# FPGA_CODECS.net
KiCad netlist of a schematic drawn in Altium Designer
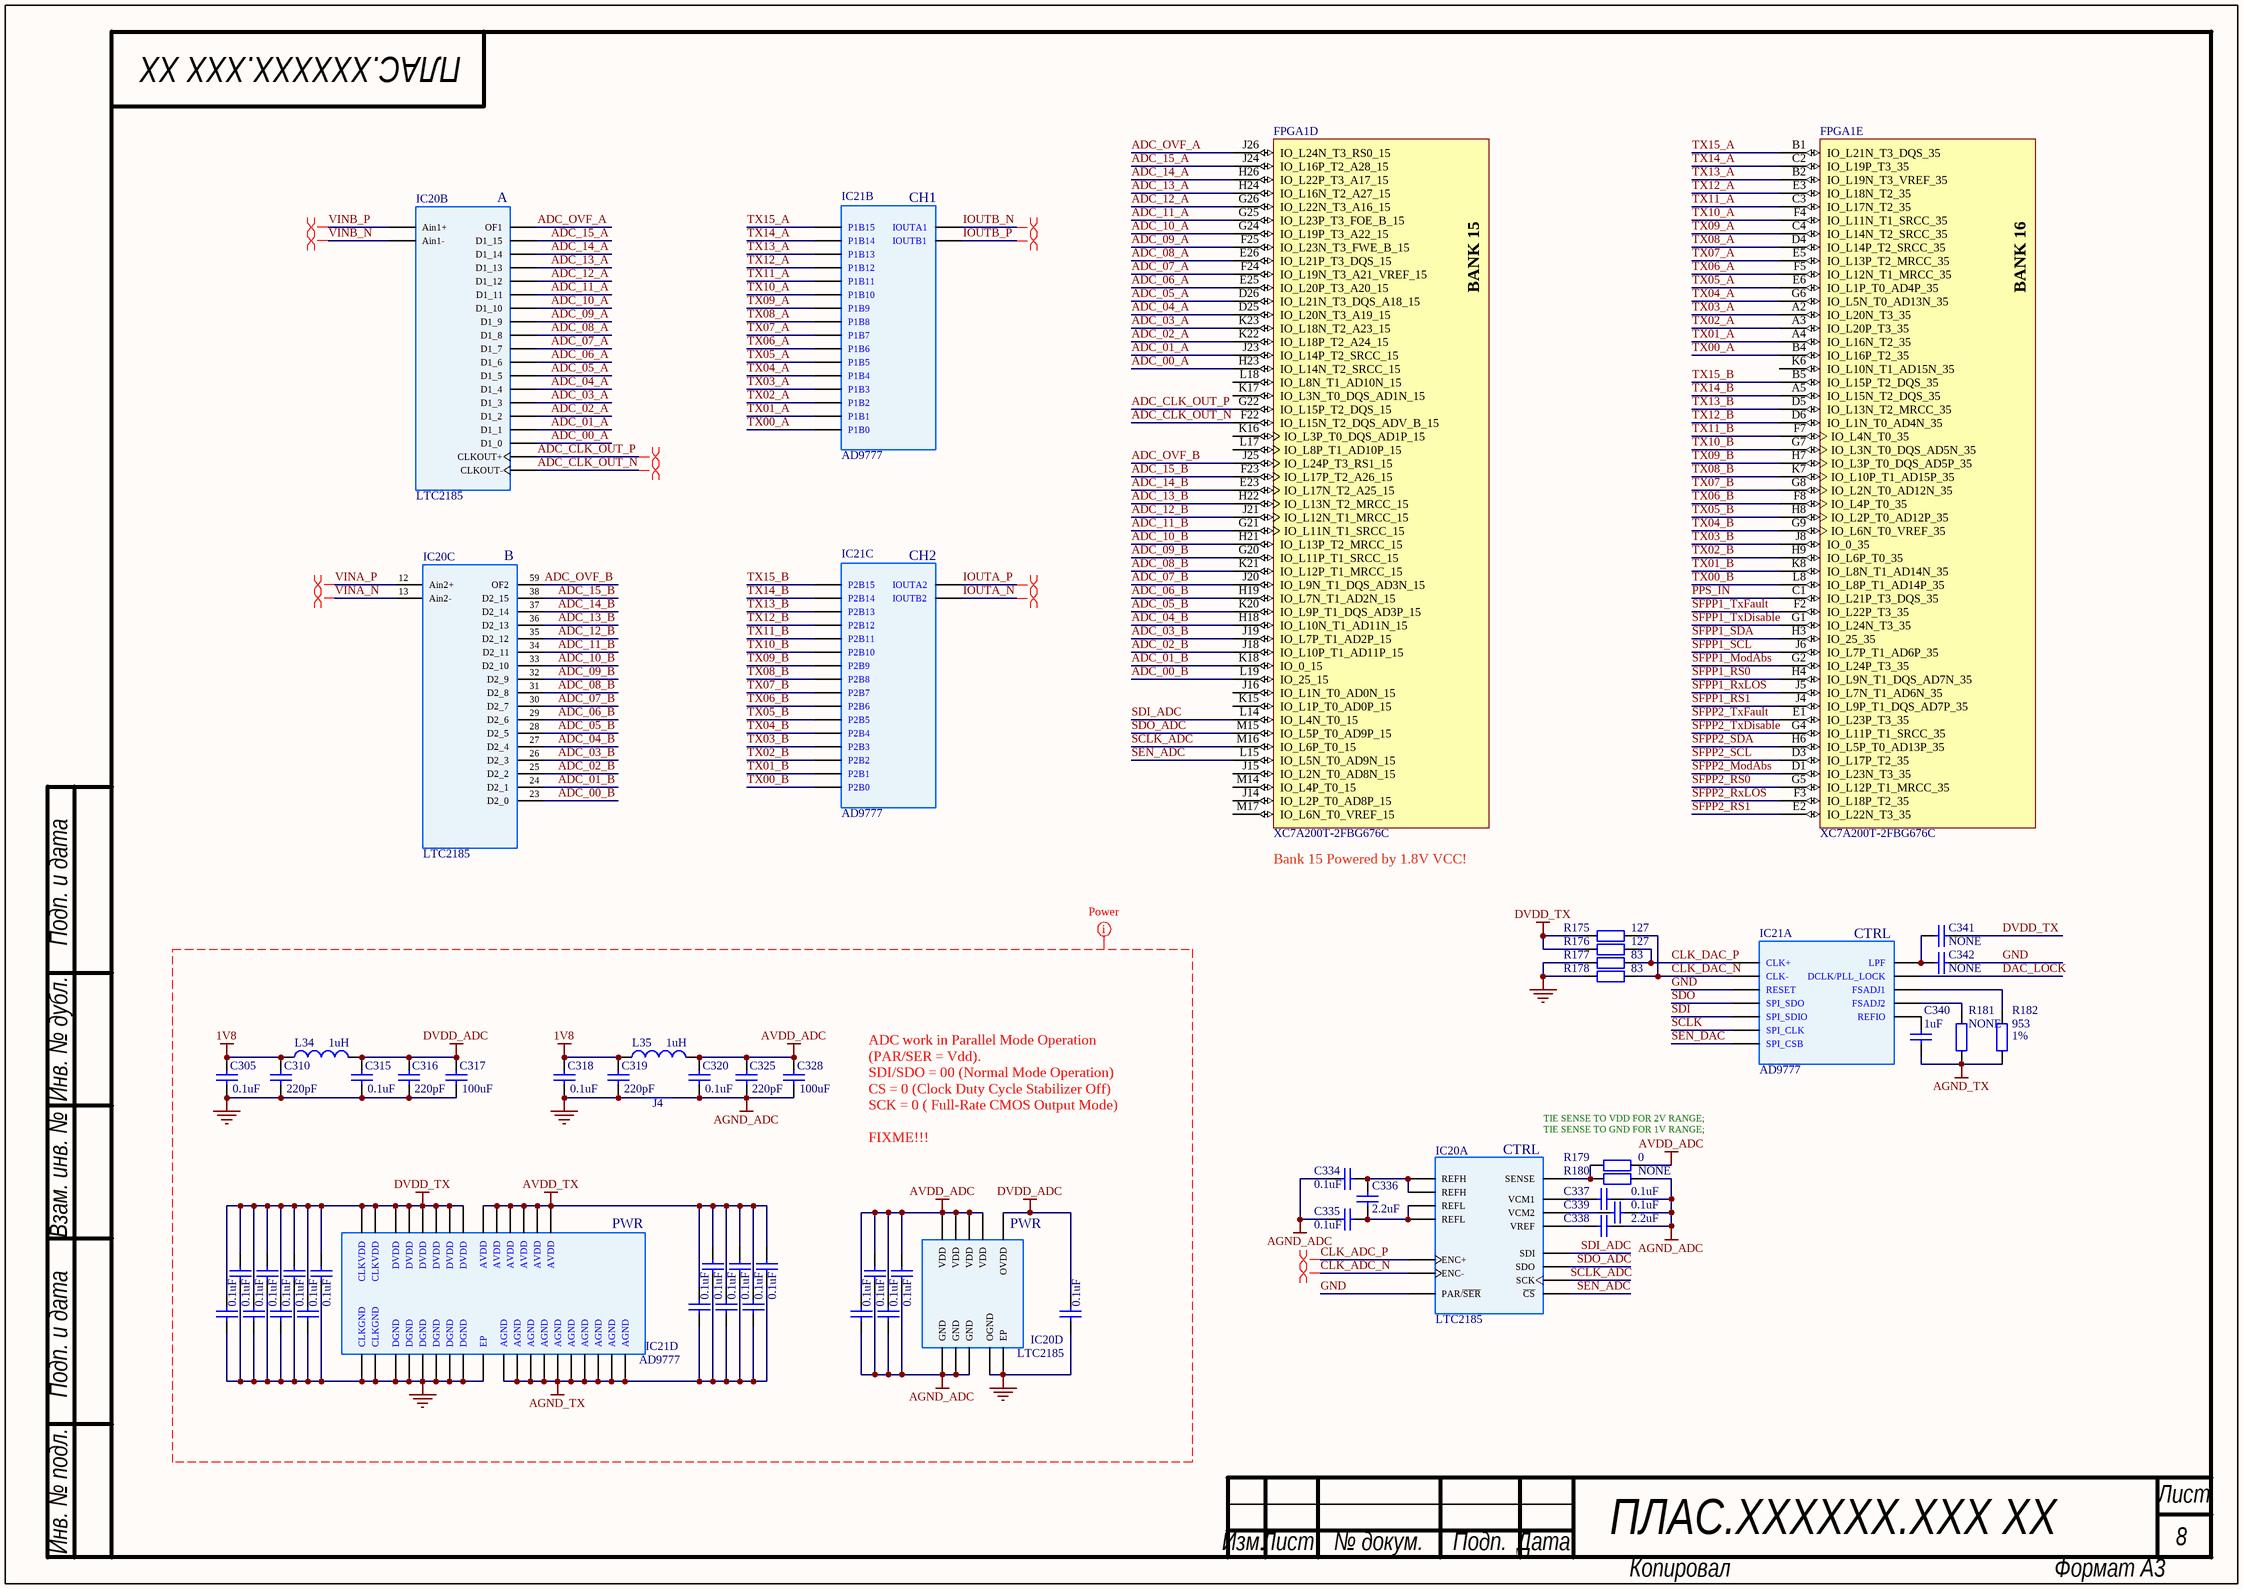
[diagram p0: FPGA&CODECS.SchDoc]

(export (version "E")
  (design (tool "Eeschema 10.0.6"))
  (components
    (comp (ref "C305")
      (value "0.1uF")
      (footprint "C0603")
      (description "Cer Cap Small")
      (fields (field (name "MANUFACTURER") "Murata") (field (name "VOLTAGE") "16V"))
      (libsource (lib "") (part "Cer Cap_1"))
    )
    (comp (ref "C306")
      (value "0.1uF")
      (footprint "С0402")
      (description "Cer Cap Small")
      (fields (field (name "MANUFACTURER") "Murata") (field (name "VOLTAGE") "50V"))
      (libsource (lib "") (part "Cer Cap_1"))
    )
    (comp (ref "C307")
      (value "0.1uF")
      (footprint "С0402")
      (description "Cer Cap Small")
      (fields (field (name "MANUFACTURER") "Murata") (field (name "VOLTAGE") "50V"))
      (libsource (lib "") (part "Cer Cap_1"))
    )
    (comp (ref "C308")
      (value "0.1uF")
      (footprint "С0402")
      (description "Cer Cap Small")
      (fields (field (name "MANUFACTURER") "Murata") (field (name "VOLTAGE") "50V"))
      (libsource (lib "") (part "Cer Cap_1"))
    )
    (comp (ref "C309")
      (value "0.1uF")
      (footprint "С0402")
      (description "Cer Cap Small")
      (fields (field (name "MANUFACTURER") "Murata") (field (name "VOLTAGE") "50V"))
      (libsource (lib "") (part "Cer Cap_1"))
    )
    (comp (ref "C310")
      (value "220pF")
      (footprint "C0603")
      (description "Cer Cap Small")
      (fields (field (name "MANUFACTURER") "Murata") (field (name "VOLTAGE") "16V"))
      (libsource (lib "") (part "Cer Cap_1"))
    )
    (comp (ref "C311")
      (value "0.1uF")
      (footprint "С0402")
      (description "Cer Cap Small")
      (fields (field (name "MANUFACTURER") "Murata") (field (name "VOLTAGE") "50V"))
      (libsource (lib "") (part "Cer Cap_1"))
    )
    (comp (ref "C312")
      (value "0.1uF")
      (footprint "С0402")
      (description "Cer Cap Small")
      (fields (field (name "MANUFACTURER") "Murata") (field (name "VOLTAGE") "50V"))
      (libsource (lib "USRP2_Clone") (part "Cer Cap"))
    )
    (comp (ref "C313")
      (value "0.1uF")
      (footprint "С0402")
      (description "Cer Cap Small")
      (fields (field (name "MANUFACTURER") "Murata") (field (name "VOLTAGE") "50V"))
      (libsource (lib "") (part "Cer Cap_1"))
    )
    (comp (ref "C314")
      (value "0.1uF")
      (footprint "С0402")
      (description "Cer Cap Small")
      (fields (field (name "MANUFACTURER") "Murata") (field (name "VOLTAGE") "50V"))
      (libsource (lib "USRP2_Clone") (part "Cer Cap"))
    )
    (comp (ref "C315")
      (value "0.1uF")
      (footprint "C0603")
      (description "Cer Cap Small")
      (fields (field (name "MANUFACTURER") "Murata") (field (name "VOLTAGE") "16V"))
      (libsource (lib "") (part "Cer Cap_1"))
    )
    (comp (ref "C316")
      (value "220pF")
      (footprint "C0603")
      (description "Cer Cap Small")
      (fields (field (name "MANUFACTURER") "Murata") (field (name "VOLTAGE") "16V"))
      (libsource (lib "") (part "Cer Cap_1"))
    )
    (comp (ref "C317")
      (value "100uF")
      (footprint "C1210")
      (description "Cer Cap Large")
      (fields (field (name "MANUFACTURER") "Murata") (field (name "TOLERANCE") "20%"))
      (libsource (lib "USRP2_Clone") (part "Cap uF"))
    )
    (comp (ref "C318")
      (value "0.1uF")
      (footprint "C0603")
      (description "Cer Cap Small")
      (fields (field (name "MANUFACTURER") "Murata") (field (name "VOLTAGE") "16V"))
      (libsource (lib "") (part "Cer Cap_1"))
    )
    (comp (ref "C319")
      (value "220pF")
      (footprint "C0603")
      (description "Cer Cap Small")
      (fields (field (name "MANUFACTURER") "Murata") (field (name "VOLTAGE") "16V"))
      (libsource (lib "") (part "Cer Cap_1"))
    )
    (comp (ref "C320")
      (value "0.1uF")
      (footprint "C0603")
      (description "Cer Cap Small")
      (fields (field (name "MANUFACTURER") "Murata") (field (name "VOLTAGE") "16V"))
      (libsource (lib "") (part "Cer Cap_1"))
    )
    (comp (ref "C321")
      (value "0.1uF")
      (footprint "С0402")
      (description "Cer Cap Small")
      (fields (field (name "MANUFACTURER") "Murata") (field (name "VOLTAGE") "50V"))
      (libsource (lib "") (part "Cer Cap_1"))
    )
    (comp (ref "C322")
      (value "0.1uF")
      (footprint "С0402")
      (description "Cer Cap Small")
      (fields (field (name "MANUFACTURER") "Murata") (field (name "VOLTAGE") "50V"))
      (libsource (lib "") (part "Cer Cap_1"))
    )
    (comp (ref "C323")
      (value "0.1uF")
      (footprint "С0402")
      (description "Cer Cap Small")
      (fields (field (name "MANUFACTURER") "Murata") (field (name "VOLTAGE") "50V"))
      (libsource (lib "") (part "Cer Cap_1"))
    )
    (comp (ref "C324")
      (value "0.1uF")
      (footprint "С0402")
      (description "Cer Cap Small")
      (fields (field (name "MANUFACTURER") "Murata") (field (name "VOLTAGE") "50V"))
      (libsource (lib "") (part "Cer Cap_1"))
    )
    (comp (ref "C325")
      (value "220pF")
      (footprint "C0603")
      (description "Cer Cap Small")
      (fields (field (name "MANUFACTURER") "Murata") (field (name "VOLTAGE") "16V"))
      (libsource (lib "") (part "Cer Cap_1"))
    )
    (comp (ref "C326")
      (value "0.1uF")
      (footprint "С0402")
      (description "Cer Cap Small")
      (fields (field (name "MANUFACTURER") "Murata") (field (name "VOLTAGE") "50V"))
      (libsource (lib "") (part "Cer Cap_1"))
    )
    (comp (ref "C327")
      (value "0.1uF")
      (footprint "С0402")
      (description "Cer Cap Small")
      (fields (field (name "MANUFACTURER") "Murata") (field (name "VOLTAGE") "50V"))
      (libsource (lib "") (part "Cer Cap_1"))
    )
    (comp (ref "C328")
      (value "100uF")
      (footprint "C1210")
      (description "Cer Cap Large")
      (fields (field (name "MANUFACTURER") "Murata") (field (name "TOLERANCE") "20%"))
      (libsource (lib "USRP2_Clone") (part "Cap uF"))
    )
    (comp (ref "C329")
      (value "0.1uF")
      (footprint "С0402")
      (description "Cer Cap Small")
      (fields (field (name "MANUFACTURER") "Murata") (field (name "VOLTAGE") "50V"))
      (libsource (lib "") (part "Cer Cap_1"))
    )
    (comp (ref "C330")
      (value "0.1uF")
      (footprint "С0402")
      (description "Cer Cap Small")
      (fields (field (name "MANUFACTURER") "Murata") (field (name "VOLTAGE") "50V"))
      (libsource (lib "") (part "Cer Cap_1"))
    )
    (comp (ref "C331")
      (value "0.1uF")
      (footprint "С0402")
      (description "Cer Cap Small")
      (fields (field (name "MANUFACTURER") "Murata") (field (name "VOLTAGE") "50V"))
      (libsource (lib "") (part "Cer Cap_1"))
    )
    (comp (ref "C332")
      (value "0.1uF")
      (footprint "С0402")
      (description "Cer Cap Small")
      (fields (field (name "MANUFACTURER") "Murata") (field (name "VOLTAGE") "50V"))
      (libsource (lib "") (part "Cer Cap_1"))
    )
    (comp (ref "C333")
      (value "0.1uF")
      (footprint "С0402")
      (description "Cer Cap Small")
      (fields (field (name "MANUFACTURER") "Murata") (field (name "VOLTAGE") "50V"))
      (libsource (lib "") (part "Cer Cap_1"))
    )
    (comp (ref "C334")
      (value "0.1uF")
      (footprint "С0402")
      (description "Cer Cap Small")
      (fields (field (name "MANUFACTURER") "Murata") (field (name "VOLTAGE") "50V"))
      (libsource (lib "USRP2_Clone") (part "Cer Cap"))
    )
    (comp (ref "C335")
      (value "0.1uF")
      (footprint "С0402")
      (description "Cer Cap Small")
      (fields (field (name "MANUFACTURER") "Murata") (field (name "VOLTAGE") "50V"))
      (libsource (lib "") (part "Cer Cap_1"))
    )
    (comp (ref "C336")
      (value "2.2uF")
      (footprint "C0603")
      (description "Cer Cap Small")
      (fields (field (name "MANUFACTURER") "Murata") (field (name "VOLTAGE") "10V"))
      (libsource (lib "USRP2_Clone") (part "Cer Cap"))
    )
    (comp (ref "C337")
      (value "0.1uF")
      (footprint "С0402")
      (description "Cer Cap Small")
      (fields (field (name "MANUFACTURER") "Murata") (field (name "VOLTAGE") "50V"))
      (libsource (lib "USRP2_Clone") (part "Cer Cap"))
    )
    (comp (ref "C338")
      (value "2.2uF")
      (footprint "C0603")
      (description "Cer Cap Small")
      (fields (field (name "MANUFACTURER") "Murata") (field (name "VOLTAGE") "10V"))
      (libsource (lib "") (part "Cer Cap_1"))
    )
    (comp (ref "C339")
      (value "0.1uF")
      (footprint "С0402")
      (description "Cer Cap Small")
      (fields (field (name "MANUFACTURER") "Murata") (field (name "VOLTAGE") "50V"))
      (libsource (lib "") (part "Cer Cap_1"))
    )
    (comp (ref "C340")
      (value "1uF")
      (footprint "С0402")
      (description "Cer Cap Small")
      (fields (field (name "MANUFACTURER") "Murata") (field (name "VOLTAGE") "16V"))
      (libsource (lib "") (part "Cer Cap_1"))
    )
    (comp (ref "C341")
      (value "NONE")
      (footprint "С0402")
      (description "Cer Cap Small")
      (fields (field (name "MANUFACTURER") "Murata") (field (name "VOLTAGE") "50V"))
      (libsource (lib "USRP2_Clone") (part "Cer Cap"))
    )
    (comp (ref "C342")
      (value "NONE")
      (footprint "С0402")
      (description "Cer Cap Small")
      (fields (field (name "MANUFACTURER") "Murata") (field (name "VOLTAGE") "50V"))
      (libsource (lib "") (part "Cer Cap_1"))
    )
    (comp (ref "FPGA1")
      (value "XC7A200T-2FBG676C")
      (footprint "FGG676")
      (description "Artix-7 FPGA, 400 User I/Os, 8 GTP, 676-Ball BGA, Speed Grade 2, Commercial Grade, Pb-Free")
      (fields (field (name "GENERIC PART NUMBER") "XC7A200T") (field (name "MANUFACTURER") "Xilinx"))
      (libsource (lib "") (part "XC7A200T-2FBG676C_1"))
    )
    (comp (ref "IC20")
      (value "LTC2185")
      (footprint "QFN-64")
      (description "Dual 16-Bit, 125Msps  Low Power 3V ADC")
      (fields (field (name "VOLTAGE") "Single 1.8V Supply"))
      (libsource (lib "USRP2_Clone") (part "LTC2185"))
    )
    (comp (ref "IC21")
      (value "AD9777")
      (footprint "TQFP-80-EP")
      (description "16-Bit, 160 MSPS  D/A Converter")
      (fields (field (name "VOLTAGE") "Single 3.3 V"))
      (libsource (lib "USRP2_Clone") (part "AD9777"))
    )
    (comp (ref "J4")
      (value "JMP")
      (footprint "JUMPER")
      (description "PGND & AGND Connect")
      (libsource (lib "USRP2_Clone") (part "JMP"))
    )
    (comp (ref "L34")
      (value "1uH")
      (footprint "L1210_Murata LQH")
      (description "Inductor_Power_Lines")
      (fields (field (name "TOLERANCE") "5%") (field (name "MANUFACTURER") "Murata"))
      (libsource (lib "USRP2_Clone") (part "Inductor_LF"))
    )
    (comp (ref "L35")
      (value "1uH")
      (footprint "L1210_Murata LQH")
      (description "Inductor_Power_Lines")
      (fields (field (name "TOLERANCE") "5%") (field (name "MANUFACTURER") "Murata"))
      (libsource (lib "") (part "Inductor_LF_1"))
    )
    (comp (ref "R175")
      (value "127")
      (footprint "R0402")
      (description "Resistor")
      (fields (field (name "TOLERANCE") "5%") (field (name "POWER") "0.062 Wt"))
      (libsource (lib "") (part "Res_1"))
    )
    (comp (ref "R176")
      (value "127")
      (footprint "R0402")
      (description "Resistor")
      (fields (field (name "TOLERANCE") "5%") (field (name "POWER") "0.062 Wt"))
      (libsource (lib "") (part "Res_1"))
    )
    (comp (ref "R177")
      (value "83")
      (footprint "R0402")
      (description "Resistor")
      (fields (field (name "TOLERANCE") "5%") (field (name "POWER") "0.062 Wt"))
      (libsource (lib "USRP2_Clone") (part "Res"))
    )
    (comp (ref "R178")
      (value "83")
      (footprint "R0402")
      (description "Resistor")
      (fields (field (name "TOLERANCE") "5%") (field (name "POWER") "0.062 Wt"))
      (libsource (lib "USRP2_Clone") (part "Res"))
    )
    (comp (ref "R179")
      (value "0")
      (footprint "R0402")
      (description "Resistor")
      (fields (field (name "TOLERANCE") "5%") (field (name "POWER") "0.062 Wt"))
      (libsource (lib "USRP2_Clone") (part "Res"))
    )
    (comp (ref "R180")
      (value "NONE")
      (footprint "R0402")
      (description "Resistor")
      (fields (field (name "TOLERANCE") "5%") (field (name "POWER") "0.062 Wt"))
      (libsource (lib "") (part "Res_2"))
    )
    (comp (ref "R181")
      (value "NONE")
      (footprint "R0402")
      (description "Resistor")
      (fields (field (name "TOLERANCE") "5%") (field (name "POWER") "0.062 Wt"))
      (libsource (lib "") (part "Res_3"))
    )
    (comp (ref "R182")
      (value "953")
      (footprint "R0402")
      (description "Resistor")
      (fields
        (field (name "TOLERANCE") "1%")
        (field (name "POWER") "0.062 Wt")
        (field (name "Comment") "Res")
      )
      (libsource (lib "") (part "Res_3"))
    )
  )
  (nets
    (net (code "1") (name "/ADC_00_A") (class "Default")
      (node (ref "FPGA1") (pin "H23") (pinfunction "IO_L14N_T2_SRCC_15_H23") (pintype "bidirectional"))
      (node (ref "IC20") (pin "43") (pinfunction "D1_0_43") (pintype "passive"))
    )
    (net (code "2") (name "/ADC_00_B") (class "Default")
      (node (ref "FPGA1") (pin "L19") (pinfunction "IO_25_15_L19") (pintype "bidirectional"))
      (node (ref "IC20") (pin "23") (pinfunction "D2_0_23") (pintype "passive"))
    )
    (net (code "3") (name "/ADC_01_A") (class "Default")
      (node (ref "FPGA1") (pin "J23") (pinfunction "IO_L14P_T2_SRCC_15_J23") (pintype "bidirectional"))
      (node (ref "IC20") (pin "44") (pinfunction "D1_1_44") (pintype "passive"))
    )
    (net (code "4") (name "/ADC_01_B") (class "Default")
      (node (ref "FPGA1") (pin "K18") (pinfunction "IO_0_15_K18") (pintype "bidirectional"))
      (node (ref "IC20") (pin "24") (pinfunction "D2_1_24") (pintype "passive"))
    )
    (net (code "5") (name "/ADC_02_A") (class "Default")
      (node (ref "FPGA1") (pin "K22") (pinfunction "IO_L18P_T2_A24_15_K22") (pintype "bidirectional"))
      (node (ref "IC20") (pin "45") (pinfunction "D1_2_45") (pintype "passive"))
    )
    (net (code "6") (name "/ADC_02_B") (class "Default")
      (node (ref "FPGA1") (pin "J18") (pinfunction "IO_L10P_T1_AD11P_15_J18") (pintype "bidirectional"))
      (node (ref "IC20") (pin "25") (pinfunction "D2_2_25") (pintype "passive"))
    )
    (net (code "7") (name "/ADC_03_A") (class "Default")
      (node (ref "FPGA1") (pin "K23") (pinfunction "IO_L18N_T2_A23_15_K23") (pintype "bidirectional"))
      (node (ref "IC20") (pin "46") (pinfunction "D1_3_46") (pintype "passive"))
    )
    (net (code "8") (name "/ADC_03_B") (class "Default")
      (node (ref "FPGA1") (pin "J19") (pinfunction "IO_L7P_T1_AD2P_15_J19") (pintype "bidirectional"))
      (node (ref "IC20") (pin "26") (pinfunction "D2_3_26") (pintype "passive"))
    )
    (net (code "9") (name "/ADC_04_A") (class "Default")
      (node (ref "FPGA1") (pin "D25") (pinfunction "IO_L20N_T3_A19_15_D25") (pintype "bidirectional"))
      (node (ref "IC20") (pin "47") (pinfunction "D1_4_47") (pintype "passive"))
    )
    (net (code "10") (name "/ADC_04_B") (class "Default")
      (node (ref "FPGA1") (pin "H18") (pinfunction "IO_L10N_T1_AD11N_15_H18") (pintype "bidirectional"))
      (node (ref "IC20") (pin "27") (pinfunction "D2_4_27") (pintype "passive"))
    )
    (net (code "11") (name "/ADC_05_A") (class "Default")
      (node (ref "FPGA1") (pin "D26") (pinfunction "IO_L21N_T3_DQS_A18_15_D26") (pintype "bidirectional"))
      (node (ref "IC20") (pin "48") (pinfunction "D1_5_48") (pintype "passive"))
    )
    (net (code "12") (name "/ADC_05_B") (class "Default")
      (node (ref "FPGA1") (pin "K20") (pinfunction "IO_L9P_T1_DQS_AD3P_15_K20") (pintype "bidirectional"))
      (node (ref "IC20") (pin "28") (pinfunction "D2_5_28") (pintype "passive"))
    )
    (net (code "13") (name "/ADC_06_A") (class "Default")
      (node (ref "FPGA1") (pin "E25") (pinfunction "IO_L20P_T3_A20_15_E25") (pintype "bidirectional"))
      (node (ref "IC20") (pin "49") (pinfunction "D1_6_49") (pintype "passive"))
    )
    (net (code "14") (name "/ADC_06_B") (class "Default")
      (node (ref "FPGA1") (pin "H19") (pinfunction "IO_L7N_T1_AD2N_15_H19") (pintype "bidirectional"))
      (node (ref "IC20") (pin "29") (pinfunction "D2_6_29") (pintype "passive"))
    )
    (net (code "15") (name "/ADC_07_A") (class "Default")
      (node (ref "FPGA1") (pin "F24") (pinfunction "IO_L19N_T3_A21_VREF_15_F24") (pintype "bidirectional"))
      (node (ref "IC20") (pin "50") (pinfunction "D1_7_50") (pintype "passive"))
    )
    (net (code "16") (name "/ADC_07_B") (class "Default")
      (node (ref "FPGA1") (pin "J20") (pinfunction "IO_L9N_T1_DQS_AD3N_15_J20") (pintype "bidirectional"))
      (node (ref "IC20") (pin "30") (pinfunction "D2_7_30") (pintype "passive"))
    )
    (net (code "17") (name "/ADC_08_A") (class "Default")
      (node (ref "FPGA1") (pin "E26") (pinfunction "IO_L21P_T3_DQS_15_E26") (pintype "bidirectional"))
      (node (ref "IC20") (pin "51") (pinfunction "D1_8_51") (pintype "passive"))
    )
    (net (code "18") (name "/ADC_08_B") (class "Default")
      (node (ref "FPGA1") (pin "K21") (pinfunction "IO_L12P_T1_MRCC_15_K21") (pintype "bidirectional"))
      (node (ref "IC20") (pin "31") (pinfunction "D2_8_31") (pintype "passive"))
    )
    (net (code "19") (name "/ADC_09_A") (class "Default")
      (node (ref "FPGA1") (pin "F25") (pinfunction "IO_L23N_T3_FWE_B_15_F25") (pintype "bidirectional"))
      (node (ref "IC20") (pin "52") (pinfunction "D1_9_52") (pintype "passive"))
    )
    (net (code "20") (name "/ADC_09_B") (class "Default")
      (node (ref "FPGA1") (pin "G20") (pinfunction "IO_L11P_T1_SRCC_15_G20") (pintype "bidirectional"))
      (node (ref "IC20") (pin "32") (pinfunction "D2_9_32") (pintype "passive"))
    )
    (net (code "21") (name "/ADC_10_A") (class "Default")
      (node (ref "FPGA1") (pin "G24") (pinfunction "IO_L19P_T3_A22_15_G24") (pintype "bidirectional"))
      (node (ref "IC20") (pin "53") (pinfunction "D1_10_53") (pintype "passive"))
    )
    (net (code "22") (name "/ADC_10_B") (class "Default")
      (node (ref "FPGA1") (pin "H21") (pinfunction "IO_L13P_T2_MRCC_15_H21") (pintype "bidirectional"))
      (node (ref "IC20") (pin "33") (pinfunction "D2_10_33") (pintype "passive"))
    )
    (net (code "23") (name "/ADC_11_A") (class "Default")
      (node (ref "FPGA1") (pin "G25") (pinfunction "IO_L23P_T3_FOE_B_15_G25") (pintype "bidirectional"))
      (node (ref "IC20") (pin "54") (pinfunction "D1_11_54") (pintype "passive"))
    )
    (net (code "24") (name "/ADC_11_B") (class "Default")
      (node (ref "FPGA1") (pin "G21") (pinfunction "IO_L11N_T1_SRCC_15_G21") (pintype "bidirectional"))
      (node (ref "IC20") (pin "34") (pinfunction "D2_11_34") (pintype "passive"))
    )
    (net (code "25") (name "/ADC_12_A") (class "Default")
      (node (ref "FPGA1") (pin "G26") (pinfunction "IO_L22N_T3_A16_15_G26") (pintype "bidirectional"))
      (node (ref "IC20") (pin "55") (pinfunction "D1_12_55") (pintype "passive"))
    )
    (net (code "26") (name "/ADC_12_B") (class "Default")
      (node (ref "FPGA1") (pin "J21") (pinfunction "IO_L12N_T1_MRCC_15_J21") (pintype "bidirectional"))
      (node (ref "IC20") (pin "35") (pinfunction "D2_12_35") (pintype "passive"))
    )
    (net (code "27") (name "/ADC_13_A") (class "Default")
      (node (ref "FPGA1") (pin "H24") (pinfunction "IO_L16N_T2_A27_15_H24") (pintype "bidirectional"))
      (node (ref "IC20") (pin "56") (pinfunction "D1_13_56") (pintype "passive"))
    )
    (net (code "28") (name "/ADC_13_B") (class "Default")
      (node (ref "FPGA1") (pin "H22") (pinfunction "IO_L13N_T2_MRCC_15_H22") (pintype "bidirectional"))
      (node (ref "IC20") (pin "36") (pinfunction "D2_13_36") (pintype "passive"))
    )
    (net (code "29") (name "/ADC_14_A") (class "Default")
      (node (ref "FPGA1") (pin "H26") (pinfunction "IO_L22P_T3_A17_15_H26") (pintype "bidirectional"))
      (node (ref "IC20") (pin "57") (pinfunction "D1_14_57") (pintype "passive"))
    )
    (net (code "30") (name "/ADC_14_B") (class "Default")
      (node (ref "FPGA1") (pin "E23") (pinfunction "IO_L17N_T2_A25_15_E23") (pintype "bidirectional"))
      (node (ref "IC20") (pin "37") (pinfunction "D2_14_37") (pintype "passive"))
    )
    (net (code "31") (name "/ADC_15_A") (class "Default")
      (node (ref "FPGA1") (pin "J24") (pinfunction "IO_L16P_T2_A28_15_J24") (pintype "bidirectional"))
      (node (ref "IC20") (pin "58") (pinfunction "D1_15_58") (pintype "passive"))
    )
    (net (code "32") (name "/ADC_15_B") (class "Default")
      (node (ref "FPGA1") (pin "F23") (pinfunction "IO_L17P_T2_A26_15_F23") (pintype "bidirectional"))
      (node (ref "IC20") (pin "38") (pinfunction "D2_15_38") (pintype "passive"))
    )
    (net (code "33") (name "/ADC_CLK_OUT_N") (class "Default")
      (node (ref "FPGA1") (pin "F22") (pinfunction "IO_L15N_T2_DQS_ADV_B_15_F22") (pintype "bidirectional"))
      (node (ref "IC20") (pin "39") (pinfunction "CLKOUT-_39") (pintype "passive"))
    )
    (net (code "34") (name "/ADC_CLK_OUT_P") (class "Default")
      (node (ref "FPGA1") (pin "G22") (pinfunction "IO_L15P_T2_DQS_15_G22") (pintype "bidirectional"))
      (node (ref "IC20") (pin "40") (pinfunction "CLKOUT+_40") (pintype "passive"))
    )
    (net (code "35") (name "/ADC_OVF_A") (class "Default")
      (node (ref "FPGA1") (pin "J26") (pinfunction "IO_L24N_T3_RS0_15_J26") (pintype "bidirectional"))
      (node (ref "IC20") (pin "60") (pinfunction "OF1_60") (pintype "passive"))
    )
    (net (code "36") (name "/ADC_OVF_B") (class "Default")
      (node (ref "FPGA1") (pin "J25") (pinfunction "IO_L24P_T3_RS1_15_J25") (pintype "bidirectional"))
      (node (ref "IC20") (pin "59") (pinfunction "OF2_59") (pintype "passive"))
    )
    (net (code "37") (name "/CLK_ADC_N") (class "Default")
      (node (ref "IC20") (pin "19") (pinfunction "ENC-_19") (pintype "passive"))
    )
    (net (code "38") (name "/CLK_ADC_P") (class "Default")
      (node (ref "IC20") (pin "18") (pinfunction "ENC+_18") (pintype "passive"))
    )
    (net (code "39") (name "/CLK_DAC_N") (class "Default")
      (node (ref "IC21") (pin "6") (pinfunction "CLK-_6") (pintype "passive"))
      (node (ref "R175") (pin "1") (pinfunction "1_1") (pintype "passive"))
      (node (ref "R178") (pin "1") (pinfunction "1_1") (pintype "passive"))
    )
    (net (code "40") (name "/CLK_DAC_P") (class "Default")
      (node (ref "IC21") (pin "5") (pinfunction "CLK+_5") (pintype "passive"))
      (node (ref "R176") (pin "1") (pinfunction "1_1") (pintype "passive"))
      (node (ref "R177") (pin "1") (pinfunction "1_1") (pintype "passive"))
    )
    (net (code "41") (name "/DAC_LOCK") (class "Default")
      (node (ref "IC21") (pin "8") (pinfunction "DCLK/PLL_LOCK_8") (pintype "passive"))
    )
    (net (code "42") (name "/IOUTA_N") (class "Default")
      (node (ref "IC21") (pin "68") (pinfunction "IOUTB2_68") (pintype "passive"))
    )
    (net (code "43") (name "/IOUTA_P") (class "Default")
      (node (ref "IC21") (pin "69") (pinfunction "IOUTA2_69") (pintype "passive"))
    )
    (net (code "44") (name "/IOUTB_N") (class "Default")
      (node (ref "IC21") (pin "73") (pinfunction "IOUTA1_73") (pintype "passive"))
    )
    (net (code "45") (name "/IOUTB_P") (class "Default")
      (node (ref "IC21") (pin "72") (pinfunction "IOUTB1_72") (pintype "passive"))
    )
    (net (code "46") (name "/PPS_IN") (class "Default")
      (node (ref "FPGA1") (pin "C1") (pinfunction "IO_L21P_T3_DQS_35_C1") (pintype "bidirectional"))
    )
    (net (code "47") (name "/SCLK") (class "Default")
      (node (ref "IC21") (pin "55") (pinfunction "SPI_CLK_55") (pintype "passive"))
    )
    (net (code "48") (name "/SCLK_ADC") (class "Default")
      (node (ref "FPGA1") (pin "M16") (pinfunction "IO_L6P_T0_15_M16") (pintype "bidirectional"))
      (node (ref "IC20") (pin "21") (pinfunction "SCK_21") (pintype "passive"))
    )
    (net (code "49") (name "/SDI") (class "Default")
      (node (ref "IC21") (pin "54") (pinfunction "SPI_SDIO_54") (pintype "passive"))
    )
    (net (code "50") (name "/SDI_ADC") (class "Default")
      (node (ref "FPGA1") (pin "L14") (pinfunction "IO_L4N_T0_15_L14") (pintype "bidirectional"))
      (node (ref "IC20") (pin "22") (pinfunction "SDI_22") (pintype "passive"))
    )
    (net (code "51") (name "/SDO") (class "Default")
      (node (ref "IC21") (pin "53") (pinfunction "SPI_SDO_53") (pintype "passive"))
    )
    (net (code "52") (name "/SDO_ADC") (class "Default")
      (node (ref "FPGA1") (pin "M15") (pinfunction "IO_L5P_T0_AD9P_15_M15") (pintype "bidirectional"))
      (node (ref "IC20") (pin "61") (pinfunction "SDO_61") (pintype "passive"))
    )
    (net (code "53") (name "/SEN_ADC") (class "Default")
      (node (ref "FPGA1") (pin "L15") (pinfunction "IO_L5N_T0_AD9N_15_L15") (pintype "bidirectional"))
      (node (ref "IC20") (pin "20") (pinfunction "~{CS}_20") (pintype "passive"))
    )
    (net (code "54") (name "/SEN_DAC") (class "Default")
      (node (ref "IC21") (pin "56") (pinfunction "SPI_CSB_56") (pintype "passive"))
    )
    (net (code "55") (name "/SFPP1_ModAbs") (class "Default")
      (node (ref "FPGA1") (pin "G2") (pinfunction "IO_L24P_T3_35_G2") (pintype "bidirectional"))
    )
    (net (code "56") (name "/SFPP1_RS0") (class "Default")
      (node (ref "FPGA1") (pin "H4") (pinfunction "IO_L9N_T1_DQS_AD7N_35_H4") (pintype "bidirectional"))
    )
    (net (code "57") (name "/SFPP1_RS1") (class "Default")
      (node (ref "FPGA1") (pin "J4") (pinfunction "IO_L9P_T1_DQS_AD7P_35_J4") (pintype "bidirectional"))
    )
    (net (code "58") (name "/SFPP1_RxLOS") (class "Default")
      (node (ref "FPGA1") (pin "J5") (pinfunction "IO_L7N_T1_AD6N_35_J5") (pintype "bidirectional"))
    )
    (net (code "59") (name "/SFPP1_SCL") (class "Default")
      (node (ref "FPGA1") (pin "J6") (pinfunction "IO_L7P_T1_AD6P_35_J6") (pintype "bidirectional"))
    )
    (net (code "60") (name "/SFPP1_SDA") (class "Default")
      (node (ref "FPGA1") (pin "H3") (pinfunction "IO_25_35_H3") (pintype "bidirectional"))
    )
    (net (code "61") (name "/SFPP1_TxDisable") (class "Default")
      (node (ref "FPGA1") (pin "G1") (pinfunction "IO_L24N_T3_35_G1") (pintype "bidirectional"))
    )
    (net (code "62") (name "/SFPP1_TxFault") (class "Default")
      (node (ref "FPGA1") (pin "F2") (pinfunction "IO_L22P_T3_35_F2") (pintype "bidirectional"))
    )
    (net (code "63") (name "/SFPP2_ModAbs") (class "Default")
      (node (ref "FPGA1") (pin "D1") (pinfunction "IO_L23N_T3_35_D1") (pintype "bidirectional"))
    )
    (net (code "64") (name "/SFPP2_RS0") (class "Default")
      (node (ref "FPGA1") (pin "G5") (pinfunction "IO_L12P_T1_MRCC_35_G5") (pintype "bidirectional"))
    )
    (net (code "65") (name "/SFPP2_RS1") (class "Default")
      (node (ref "FPGA1") (pin "E2") (pinfunction "IO_L22N_T3_35_E2") (pintype "bidirectional"))
    )
    (net (code "66") (name "/SFPP2_RxLOS") (class "Default")
      (node (ref "FPGA1") (pin "F3") (pinfunction "IO_L18P_T2_35_F3") (pintype "bidirectional"))
    )
    (net (code "67") (name "/SFPP2_SCL") (class "Default")
      (node (ref "FPGA1") (pin "D3") (pinfunction "IO_L17P_T2_35_D3") (pintype "bidirectional"))
    )
    (net (code "68") (name "/SFPP2_SDA") (class "Default")
      (node (ref "FPGA1") (pin "H6") (pinfunction "IO_L5P_T0_AD13P_35_H6") (pintype "bidirectional"))
    )
    (net (code "69") (name "/SFPP2_TxDisable") (class "Default")
      (node (ref "FPGA1") (pin "G4") (pinfunction "IO_L11P_T1_SRCC_35_G4") (pintype "bidirectional"))
    )
    (net (code "70") (name "/SFPP2_TxFault") (class "Default")
      (node (ref "FPGA1") (pin "E1") (pinfunction "IO_L23P_T3_35_E1") (pintype "bidirectional"))
    )
    (net (code "71") (name "/TX00_A") (class "Default")
      (node (ref "FPGA1") (pin "B4") (pinfunction "IO_L16P_T2_35_B4") (pintype "bidirectional"))
      (node (ref "IC21") (pin "30") (pinfunction "P1B0_30") (pintype "passive"))
    )
    (net (code "72") (name "/TX00_B") (class "Default")
      (node (ref "FPGA1") (pin "L8") (pinfunction "IO_L8P_T1_AD14P_35_L8") (pintype "bidirectional"))
      (node (ref "IC21") (pin "50") (pinfunction "P2B0_50") (pintype "passive"))
    )
    (net (code "73") (name "/TX01_A") (class "Default")
      (node (ref "FPGA1") (pin "A4") (pinfunction "IO_L16N_T2_35_A4") (pintype "bidirectional"))
      (node (ref "IC21") (pin "29") (pinfunction "P1B1_29") (pintype "passive"))
    )
    (net (code "74") (name "/TX01_B") (class "Default")
      (node (ref "FPGA1") (pin "K8") (pinfunction "IO_L8N_T1_AD14N_35_K8") (pintype "bidirectional"))
      (node (ref "IC21") (pin "49") (pinfunction "P2B1_49") (pintype "passive"))
    )
    (net (code "75") (name "/TX02_A") (class "Default")
      (node (ref "FPGA1") (pin "A3") (pinfunction "IO_L20P_T3_35_A3") (pintype "bidirectional"))
      (node (ref "IC21") (pin "28") (pinfunction "P1B2_28") (pintype "passive"))
    )
    (net (code "76") (name "/TX02_B") (class "Default")
      (node (ref "FPGA1") (pin "H9") (pinfunction "IO_L6P_T0_35_H9") (pintype "bidirectional"))
      (node (ref "IC21") (pin "48") (pinfunction "P2B2_48") (pintype "passive"))
    )
    (net (code "77") (name "/TX03_A") (class "Default")
      (node (ref "FPGA1") (pin "A2") (pinfunction "IO_L20N_T3_35_A2") (pintype "bidirectional"))
      (node (ref "IC21") (pin "27") (pinfunction "P1B3_27") (pintype "passive"))
    )
    (net (code "78") (name "/TX03_B") (class "Default")
      (node (ref "FPGA1") (pin "J8") (pinfunction "IO_0_35_J8") (pintype "bidirectional"))
      (node (ref "IC21") (pin "47") (pinfunction "P2B3_47") (pintype "passive"))
    )
    (net (code "79") (name "/TX04_A") (class "Default")
      (node (ref "FPGA1") (pin "G6") (pinfunction "IO_L5N_T0_AD13N_35_G6") (pintype "bidirectional"))
      (node (ref "IC21") (pin "24") (pinfunction "P1B4_24") (pintype "passive"))
    )
    (net (code "80") (name "/TX04_B") (class "Default")
      (node (ref "FPGA1") (pin "G9") (pinfunction "IO_L6N_T0_VREF_35_G9") (pintype "bidirectional"))
      (node (ref "IC21") (pin "46") (pinfunction "P2B4_46") (pintype "passive"))
    )
    (net (code "81") (name "/TX05_A") (class "Default")
      (node (ref "FPGA1") (pin "E6") (pinfunction "IO_L1P_T0_AD4P_35_E6") (pintype "bidirectional"))
      (node (ref "IC21") (pin "23") (pinfunction "P1B5_23") (pintype "passive"))
    )
    (net (code "82") (name "/TX05_B") (class "Default")
      (node (ref "FPGA1") (pin "H8") (pinfunction "IO_L2P_T0_AD12P_35_H8") (pintype "bidirectional"))
      (node (ref "IC21") (pin "45") (pinfunction "P2B5_45") (pintype "passive"))
    )
    (net (code "83") (name "/TX06_A") (class "Default")
      (node (ref "FPGA1") (pin "F5") (pinfunction "IO_L12N_T1_MRCC_35_F5") (pintype "bidirectional"))
      (node (ref "IC21") (pin "22") (pinfunction "P1B6_22") (pintype "passive"))
    )
    (net (code "84") (name "/TX06_B") (class "Default")
      (node (ref "FPGA1") (pin "F8") (pinfunction "IO_L4P_T0_35_F8") (pintype "bidirectional"))
      (node (ref "IC21") (pin "42") (pinfunction "P2B6_42") (pintype "passive"))
    )
    (net (code "85") (name "/TX07_A") (class "Default")
      (node (ref "FPGA1") (pin "E5") (pinfunction "IO_L13P_T2_MRCC_35_E5") (pintype "bidirectional"))
      (node (ref "IC21") (pin "21") (pinfunction "P1B7_21") (pintype "passive"))
    )
    (net (code "86") (name "/TX07_B") (class "Default")
      (node (ref "FPGA1") (pin "G8") (pinfunction "IO_L2N_T0_AD12N_35_G8") (pintype "bidirectional"))
      (node (ref "IC21") (pin "41") (pinfunction "P2B7_41") (pintype "passive"))
    )
    (net (code "87") (name "/TX08_A") (class "Default")
      (node (ref "FPGA1") (pin "D4") (pinfunction "IO_L14P_T2_SRCC_35_D4") (pintype "bidirectional"))
      (node (ref "IC21") (pin "20") (pinfunction "P1B8_20") (pintype "passive"))
    )
    (net (code "88") (name "/TX08_B") (class "Default")
      (node (ref "FPGA1") (pin "K7") (pinfunction "IO_L10P_T1_AD15P_35_K7") (pintype "bidirectional"))
      (node (ref "IC21") (pin "40") (pinfunction "P2B8_40") (pintype "passive"))
    )
    (net (code "89") (name "/TX09_A") (class "Default")
      (node (ref "FPGA1") (pin "C4") (pinfunction "IO_L14N_T2_SRCC_35_C4") (pintype "bidirectional"))
      (node (ref "IC21") (pin "19") (pinfunction "P1B9_19") (pintype "passive"))
    )
    (net (code "90") (name "/TX09_B") (class "Default")
      (node (ref "FPGA1") (pin "H7") (pinfunction "IO_L3P_T0_DQS_AD5P_35_H7") (pintype "bidirectional"))
      (node (ref "IC21") (pin "39") (pinfunction "P2B9_39") (pintype "passive"))
    )
    (net (code "91") (name "/TX10_A") (class "Default")
      (node (ref "FPGA1") (pin "F4") (pinfunction "IO_L11N_T1_SRCC_35_F4") (pintype "bidirectional"))
      (node (ref "IC21") (pin "16") (pinfunction "P1B10_16") (pintype "passive"))
    )
    (net (code "92") (name "/TX10_B") (class "Default")
      (node (ref "FPGA1") (pin "G7") (pinfunction "IO_L3N_T0_DQS_AD5N_35_G7") (pintype "bidirectional"))
      (node (ref "IC21") (pin "38") (pinfunction "P2B10_38") (pintype "passive"))
    )
    (net (code "93") (name "/TX11_A") (class "Default")
      (node (ref "FPGA1") (pin "C3") (pinfunction "IO_L17N_T2_35_C3") (pintype "bidirectional"))
      (node (ref "IC21") (pin "15") (pinfunction "P1B11_15") (pintype "passive"))
    )
    (net (code "94") (name "/TX11_B") (class "Default")
      (node (ref "FPGA1") (pin "F7") (pinfunction "IO_L4N_T0_35_F7") (pintype "bidirectional"))
      (node (ref "IC21") (pin "37") (pinfunction "P2B11_37") (pintype "passive"))
    )
    (net (code "95") (name "/TX12_A") (class "Default")
      (node (ref "FPGA1") (pin "E3") (pinfunction "IO_L18N_T2_35_E3") (pintype "bidirectional"))
      (node (ref "IC21") (pin "14") (pinfunction "P1B12_14") (pintype "passive"))
    )
    (net (code "96") (name "/TX12_B") (class "Default")
      (node (ref "FPGA1") (pin "D6") (pinfunction "IO_L1N_T0_AD4N_35_D6") (pintype "bidirectional"))
      (node (ref "IC21") (pin "34") (pinfunction "P2B12_34") (pintype "passive"))
    )
    (net (code "97") (name "/TX13_A") (class "Default")
      (node (ref "FPGA1") (pin "B2") (pinfunction "IO_L19N_T3_VREF_35_B2") (pintype "bidirectional"))
      (node (ref "IC21") (pin "13") (pinfunction "P1B13_13") (pintype "passive"))
    )
    (net (code "98") (name "/TX13_B") (class "Default")
      (node (ref "FPGA1") (pin "D5") (pinfunction "IO_L13N_T2_MRCC_35_D5") (pintype "bidirectional"))
      (node (ref "IC21") (pin "33") (pinfunction "P2B13_33") (pintype "passive"))
    )
    (net (code "99") (name "/TX14_A") (class "Default")
      (node (ref "FPGA1") (pin "C2") (pinfunction "IO_L19P_T3_35_C2") (pintype "bidirectional"))
      (node (ref "IC21") (pin "12") (pinfunction "P1B14_12") (pintype "passive"))
    )
    (net (code "100") (name "/TX14_B") (class "Default")
      (node (ref "FPGA1") (pin "A5") (pinfunction "IO_L15N_T2_DQS_35_A5") (pintype "bidirectional"))
      (node (ref "IC21") (pin "32") (pinfunction "P2B14_32") (pintype "passive"))
    )
    (net (code "101") (name "/TX15_A") (class "Default")
      (node (ref "FPGA1") (pin "B1") (pinfunction "IO_L21N_T3_DQS_35_B1") (pintype "bidirectional"))
      (node (ref "IC21") (pin "11") (pinfunction "P1B15_11") (pintype "passive"))
    )
    (net (code "102") (name "/TX15_B") (class "Default")
      (node (ref "FPGA1") (pin "B5") (pinfunction "IO_L15P_T2_DQS_35_B5") (pintype "bidirectional"))
      (node (ref "IC21") (pin "31") (pinfunction "P2B15_31") (pintype "passive"))
    )
    (net (code "103") (name "/VINA_N") (class "Default")
      (node (ref "IC20") (pin "13") (pinfunction "Ain2-_13") (pintype "passive"))
    )
    (net (code "104") (name "/VINA_P") (class "Default")
      (node (ref "IC20") (pin "12") (pinfunction "Ain2+_12") (pintype "passive"))
    )
    (net (code "105") (name "/VINB_N") (class "Default")
      (node (ref "IC20") (pin "5") (pinfunction "Ain1-_5") (pintype "passive"))
    )
    (net (code "106") (name "/VINB_P") (class "Default")
      (node (ref "IC20") (pin "4") (pinfunction "Ain1+_4") (pintype "passive"))
    )
    (net (code "107") (name "1V8") (class "Default")
      (node (ref "C305") (pin "1") (pinfunction "1_1") (pintype "passive"))
      (node (ref "C310") (pin "1") (pinfunction "1_1") (pintype "passive"))
      (node (ref "C318") (pin "1") (pinfunction "1_1") (pintype "passive"))
      (node (ref "C319") (pin "1") (pinfunction "1_1") (pintype "passive"))
      (node (ref "L34") (pin "2") (pinfunction "2_2") (pintype "passive"))
      (node (ref "L35") (pin "1") (pinfunction "1_1") (pintype "passive"))
    )
    (net (code "108") (name "AGND_ADC") (class "Default")
      (node (ref "C320") (pin "2") (pinfunction "2_2") (pintype "passive"))
      (node (ref "C325") (pin "2") (pinfunction "2_2") (pintype "passive"))
      (node (ref "C328") (pin "2") (pinfunction "2_2") (pintype "passive"))
      (node (ref "C329") (pin "1") (pinfunction "1_1") (pintype "passive"))
      (node (ref "C330") (pin "1") (pinfunction "1_1") (pintype "passive"))
      (node (ref "C331") (pin "1") (pinfunction "1_1") (pintype "passive"))
      (node (ref "C332") (pin "1") (pinfunction "1_1") (pintype "passive"))
      (node (ref "C334") (pin "1") (pinfunction "1_1") (pintype "passive"))
      (node (ref "C335") (pin "2") (pinfunction "2_2") (pintype "passive"))
      (node (ref "C337") (pin "2") (pinfunction "2_2") (pintype "passive"))
      (node (ref "C338") (pin "1") (pinfunction "1_1") (pintype "passive"))
      (node (ref "C339") (pin "1") (pinfunction "1_1") (pintype "passive"))
      (node (ref "IC20") (pin "14") (pinfunction "GND_14") (pintype "power_in"))
      (node (ref "IC20") (pin "3") (pinfunction "GND_3") (pintype "power_in"))
      (node (ref "IC20") (pin "6") (pinfunction "GND_6") (pintype "power_in"))
      (node (ref "J4") (pin "2") (pinfunction "2_2") (pintype "passive"))
      (node (ref "R180") (pin "2") (pinfunction "2_2") (pintype "passive"))
    )
    (net (code "109") (name "AGND_TX") (class "Default")
      (node (ref "C321") (pin "1") (pinfunction "1_1") (pintype "passive"))
      (node (ref "C322") (pin "1") (pinfunction "1_1") (pintype "passive"))
      (node (ref "C323") (pin "1") (pinfunction "1_1") (pintype "passive"))
      (node (ref "C324") (pin "1") (pinfunction "1_1") (pintype "passive"))
      (node (ref "C326") (pin "1") (pinfunction "1_1") (pintype "passive"))
      (node (ref "C327") (pin "1") (pinfunction "1_1") (pintype "passive"))
      (node (ref "C340") (pin "2") (pinfunction "2_2") (pintype "passive"))
      (node (ref "IC21") (pin "62") (pinfunction "AGND_62") (pintype "passive"))
      (node (ref "IC21") (pin "64") (pinfunction "AGND_64") (pintype "passive"))
      (node (ref "IC21") (pin "66") (pinfunction "AGND_66") (pintype "passive"))
      (node (ref "IC21") (pin "67") (pinfunction "AGND_67") (pintype "passive"))
      (node (ref "IC21") (pin "70") (pinfunction "AGND_70") (pintype "passive"))
      (node (ref "IC21") (pin "71") (pinfunction "AGND_71") (pintype "passive"))
      (node (ref "IC21") (pin "74") (pinfunction "AGND_74") (pintype "passive"))
      (node (ref "IC21") (pin "75") (pinfunction "AGND_75") (pintype "passive"))
      (node (ref "IC21") (pin "77") (pinfunction "AGND_77") (pintype "passive"))
      (node (ref "IC21") (pin "79") (pinfunction "AGND_79") (pintype "passive"))
      (node (ref "R181") (pin "2") (pinfunction "2_2") (pintype "passive"))
      (node (ref "R182") (pin "2") (pinfunction "2_2") (pintype "passive"))
    )
    (net (code "110") (name "AVDD_ADC") (class "Default")
      (node (ref "C320") (pin "1") (pinfunction "1_1") (pintype "passive"))
      (node (ref "C325") (pin "1") (pinfunction "1_1") (pintype "passive"))
      (node (ref "C328") (pin "1") (pinfunction "1_1") (pintype "passive"))
      (node (ref "C329") (pin "2") (pinfunction "2_2") (pintype "passive"))
      (node (ref "C330") (pin "2") (pinfunction "2_2") (pintype "passive"))
      (node (ref "C331") (pin "2") (pinfunction "2_2") (pintype "passive"))
      (node (ref "C332") (pin "2") (pinfunction "2_2") (pintype "passive"))
      (node (ref "IC20") (pin "1") (pinfunction "VDD_1") (pintype "power_in"))
      (node (ref "IC20") (pin "16") (pinfunction "VDD_16") (pintype "power_in"))
      (node (ref "IC20") (pin "17") (pinfunction "VDD_17") (pintype "power_in"))
      (node (ref "IC20") (pin "64") (pinfunction "VDD_64") (pintype "power_in"))
      (node (ref "L35") (pin "2") (pinfunction "2_2") (pintype "passive"))
      (node (ref "R179") (pin "1") (pinfunction "1_1") (pintype "passive"))
    )
    (net (code "111") (name "AVDD_TX") (class "Default")
      (node (ref "C321") (pin "2") (pinfunction "2_2") (pintype "passive"))
      (node (ref "C322") (pin "2") (pinfunction "2_2") (pintype "passive"))
      (node (ref "C323") (pin "2") (pinfunction "2_2") (pintype "passive"))
      (node (ref "C324") (pin "2") (pinfunction "2_2") (pintype "passive"))
      (node (ref "C326") (pin "2") (pinfunction "2_2") (pintype "passive"))
      (node (ref "C327") (pin "2") (pinfunction "2_2") (pintype "passive"))
      (node (ref "IC21") (pin "61") (pinfunction "AVDD_61") (pintype "passive"))
      (node (ref "IC21") (pin "63") (pinfunction "AVDD_63") (pintype "passive"))
      (node (ref "IC21") (pin "65") (pinfunction "AVDD_65") (pintype "passive"))
      (node (ref "IC21") (pin "76") (pinfunction "AVDD_76") (pintype "passive"))
      (node (ref "IC21") (pin "78") (pinfunction "AVDD_78") (pintype "passive"))
      (node (ref "IC21") (pin "80") (pinfunction "AVDD_80") (pintype "passive"))
    )
    (net (code "112") (name "DVDD_ADC") (class "Default")
      (node (ref "C315") (pin "1") (pinfunction "1_1") (pintype "passive"))
      (node (ref "C316") (pin "1") (pinfunction "1_1") (pintype "passive"))
      (node (ref "C317") (pin "1") (pinfunction "1_1") (pintype "passive"))
      (node (ref "C333") (pin "2") (pinfunction "2_2") (pintype "passive"))
      (node (ref "IC20") (pin "42") (pinfunction "OVDD_42") (pintype "power_in"))
      (node (ref "L34") (pin "1") (pinfunction "1_1") (pintype "passive"))
    )
    (net (code "113") (name "DVDD_TX") (class "Default")
      (node (ref "C306") (pin "2") (pinfunction "2_2") (pintype "passive"))
      (node (ref "C307") (pin "2") (pinfunction "2_2") (pintype "passive"))
      (node (ref "C308") (pin "2") (pinfunction "2_2") (pintype "passive"))
      (node (ref "C309") (pin "2") (pinfunction "2_2") (pintype "passive"))
      (node (ref "C311") (pin "2") (pinfunction "2_2") (pintype "passive"))
      (node (ref "C312") (pin "1") (pinfunction "1_1") (pintype "passive"))
      (node (ref "C313") (pin "2") (pinfunction "2_2") (pintype "passive"))
      (node (ref "C314") (pin "1") (pinfunction "1_1") (pintype "passive"))
      (node (ref "C341") (pin "2") (pinfunction "2_2") (pintype "passive"))
      (node (ref "IC21") (pin "1") (pinfunction "CLKVDD_1") (pintype "passive"))
      (node (ref "IC21") (pin "10") (pinfunction "DVDD_10") (pintype "passive"))
      (node (ref "IC21") (pin "18") (pinfunction "DVDD_18") (pintype "passive"))
      (node (ref "IC21") (pin "26") (pinfunction "DVDD_26") (pintype "passive"))
      (node (ref "IC21") (pin "3") (pinfunction "CLKVDD_3") (pintype "passive"))
      (node (ref "IC21") (pin "36") (pinfunction "DVDD_36") (pintype "passive"))
      (node (ref "IC21") (pin "43") (pinfunction "DVDD_43") (pintype "passive"))
      (node (ref "IC21") (pin "51") (pinfunction "DVDD_51") (pintype "passive"))
      (node (ref "R175") (pin "2") (pinfunction "2_2") (pintype "passive"))
      (node (ref "R176") (pin "2") (pinfunction "2_2") (pintype "passive"))
    )
    (net (code "114") (name "GND") (class "Default")
      (node (ref "C305") (pin "2") (pinfunction "2_2") (pintype "passive"))
      (node (ref "C306") (pin "1") (pinfunction "1_1") (pintype "passive"))
      (node (ref "C307") (pin "1") (pinfunction "1_1") (pintype "passive"))
      (node (ref "C308") (pin "1") (pinfunction "1_1") (pintype "passive"))
      (node (ref "C309") (pin "1") (pinfunction "1_1") (pintype "passive"))
      (node (ref "C310") (pin "2") (pinfunction "2_2") (pintype "passive"))
      (node (ref "C311") (pin "1") (pinfunction "1_1") (pintype "passive"))
      (node (ref "C312") (pin "2") (pinfunction "2_2") (pintype "passive"))
      (node (ref "C313") (pin "1") (pinfunction "1_1") (pintype "passive"))
      (node (ref "C314") (pin "2") (pinfunction "2_2") (pintype "passive"))
      (node (ref "C315") (pin "2") (pinfunction "2_2") (pintype "passive"))
      (node (ref "C316") (pin "2") (pinfunction "2_2") (pintype "passive"))
      (node (ref "C317") (pin "2") (pinfunction "2_2") (pintype "passive"))
      (node (ref "C318") (pin "2") (pinfunction "2_2") (pintype "passive"))
      (node (ref "C319") (pin "2") (pinfunction "2_2") (pintype "passive"))
      (node (ref "C333") (pin "1") (pinfunction "1_1") (pintype "passive"))
      (node (ref "C342") (pin "1") (pinfunction "1_1") (pintype "passive"))
      (node (ref "IC20") (pin "0") (pinfunction "EP_0") (pintype "power_in"))
      (node (ref "IC20") (pin "11") (pinfunction "PAR/~{SER}_11") (pintype "passive"))
      (node (ref "IC20") (pin "41") (pinfunction "OGND_41") (pintype "power_in"))
      (node (ref "IC21") (pin "0") (pinfunction "EP_0") (pintype "passive"))
      (node (ref "IC21") (pin "17") (pinfunction "DGND_17") (pintype "passive"))
      (node (ref "IC21") (pin "25") (pinfunction "DGND_25") (pintype "passive"))
      (node (ref "IC21") (pin "35") (pinfunction "DGND_35") (pintype "passive"))
      (node (ref "IC21") (pin "4") (pinfunction "CLKGND_4") (pintype "passive"))
      (node (ref "IC21") (pin "44") (pinfunction "DGND_44") (pintype "passive"))
      (node (ref "IC21") (pin "52") (pinfunction "DGND_52") (pintype "passive"))
      (node (ref "IC21") (pin "57") (pinfunction "RESET_57") (pintype "passive"))
      (node (ref "IC21") (pin "7") (pinfunction "CLKGND_7") (pintype "passive"))
      (node (ref "IC21") (pin "9") (pinfunction "DGND_9") (pintype "passive"))
      (node (ref "J4") (pin "1") (pinfunction "1_1") (pintype "passive"))
      (node (ref "R177") (pin "2") (pinfunction "2_2") (pintype "passive"))
      (node (ref "R178") (pin "2") (pinfunction "2_2") (pintype "passive"))
    )
    (net (code "115") (name "Net-(C334-Pad2)") (class "Default")
      (node (ref "C334") (pin "2") (pinfunction "2_2") (pintype "passive"))
      (node (ref "C336") (pin "1") (pinfunction "1_1") (pintype "passive"))
      (node (ref "IC20") (pin "7") (pinfunction "REFH_7") (pintype "passive"))
      (node (ref "IC20") (pin "9") (pinfunction "REFH_9") (pintype "passive"))
    )
    (net (code "116") (name "Net-(C335-Pad1)") (class "Default")
      (node (ref "C335") (pin "1") (pinfunction "1_1") (pintype "passive"))
      (node (ref "C336") (pin "2") (pinfunction "2_2") (pintype "passive"))
      (node (ref "IC20") (pin "10") (pinfunction "REFL_10") (pintype "passive"))
      (node (ref "IC20") (pin "8") (pinfunction "REFL_8") (pintype "passive"))
    )
    (net (code "117") (name "Net-(IC20A-SENSE)") (class "Default")
      (node (ref "IC20") (pin "63") (pinfunction "SENSE_63") (pintype "passive"))
      (node (ref "R179") (pin "2") (pinfunction "2_2") (pintype "passive"))
      (node (ref "R180") (pin "1") (pinfunction "1_1") (pintype "passive"))
    )
    (net (code "118") (name "Net-(IC20A-VCM1)") (class "Default")
      (node (ref "C337") (pin "1") (pinfunction "1_1") (pintype "passive"))
      (node (ref "IC20") (pin "2") (pinfunction "VCM1_2") (pintype "passive"))
    )
    (net (code "119") (name "Net-(IC20A-VCM2)") (class "Default")
      (node (ref "C339") (pin "2") (pinfunction "2_2") (pintype "passive"))
      (node (ref "IC20") (pin "15") (pinfunction "VCM2_15") (pintype "passive"))
    )
    (net (code "120") (name "Net-(IC20A-VREF)") (class "Default")
      (node (ref "C338") (pin "2") (pinfunction "2_2") (pintype "passive"))
      (node (ref "IC20") (pin "62") (pinfunction "VREF_62") (pintype "passive"))
    )
    (net (code "121") (name "Net-(IC21A-FSADJ1)") (class "Default")
      (node (ref "IC21") (pin "60") (pinfunction "FSADJ1_60") (pintype "passive"))
      (node (ref "R182") (pin "1") (pinfunction "1_1") (pintype "passive"))
    )
    (net (code "122") (name "Net-(IC21A-FSADJ2)") (class "Default")
      (node (ref "IC21") (pin "59") (pinfunction "FSADJ2_59") (pintype "passive"))
      (node (ref "R181") (pin "1") (pinfunction "1_1") (pintype "passive"))
    )
    (net (code "123") (name "Net-(IC21A-LPF)") (class "Default")
      (node (ref "C341") (pin "1") (pinfunction "1_1") (pintype "passive"))
      (node (ref "C342") (pin "2") (pinfunction "2_2") (pintype "passive"))
      (node (ref "IC21") (pin "2") (pinfunction "LPF_2") (pintype "passive"))
    )
    (net (code "124") (name "Net-(IC21A-REFIO)") (class "Default")
      (node (ref "C340") (pin "1") (pinfunction "1_1") (pintype "passive"))
      (node (ref "IC21") (pin "58") (pinfunction "REFIO_58") (pintype "passive"))
    )
    (net (code "125") (name "unconnected-(FPGA1D-IO_L1N_T0_AD0N_15-PadJ16)") (class "Default")
      (node (ref "FPGA1") (pin "J16") (pinfunction "IO_L1N_T0_AD0N_15_J16") (pintype "bidirectional"))
    )
    (net (code "126") (name "unconnected-(FPGA1D-IO_L1P_T0_AD0P_15-PadK15)") (class "Default")
      (node (ref "FPGA1") (pin "K15") (pinfunction "IO_L1P_T0_AD0P_15_K15") (pintype "bidirectional"))
    )
    (net (code "127") (name "unconnected-(FPGA1D-IO_L2N_T0_AD8N_15-PadJ15)") (class "Default")
      (node (ref "FPGA1") (pin "J15") (pinfunction "IO_L2N_T0_AD8N_15_J15") (pintype "bidirectional"))
    )
    (net (code "128") (name "unconnected-(FPGA1D-IO_L2P_T0_AD8P_15-PadJ14)") (class "Default")
      (node (ref "FPGA1") (pin "J14") (pinfunction "IO_L2P_T0_AD8P_15_J14") (pintype "bidirectional"))
    )
    (net (code "129") (name "unconnected-(FPGA1D-IO_L3N_T0_DQS_AD1N_15-PadK17)") (class "Default")
      (node (ref "FPGA1") (pin "K17") (pinfunction "IO_L3N_T0_DQS_AD1N_15_K17") (pintype "bidirectional"))
    )
    (net (code "130") (name "unconnected-(FPGA1D-IO_L3P_T0_DQS_AD1P_15-PadK16)") (class "Default")
      (node (ref "FPGA1") (pin "K16") (pinfunction "IO_L3P_T0_DQS_AD1P_15_K16") (pintype "bidirectional"))
    )
    (net (code "131") (name "unconnected-(FPGA1D-IO_L4P_T0_15-PadM14)") (class "Default")
      (node (ref "FPGA1") (pin "M14") (pinfunction "IO_L4P_T0_15_M14") (pintype "bidirectional"))
    )
    (net (code "132") (name "unconnected-(FPGA1D-IO_L6N_T0_VREF_15-PadM17)") (class "Default")
      (node (ref "FPGA1") (pin "M17") (pinfunction "IO_L6N_T0_VREF_15_M17") (pintype "bidirectional"))
    )
    (net (code "133") (name "unconnected-(FPGA1D-IO_L8N_T1_AD10N_15-PadL18)") (class "Default")
      (node (ref "FPGA1") (pin "L18") (pinfunction "IO_L8N_T1_AD10N_15_L18") (pintype "bidirectional"))
    )
    (net (code "134") (name "unconnected-(FPGA1D-IO_L8P_T1_AD10P_15-PadL17)") (class "Default")
      (node (ref "FPGA1") (pin "L17") (pinfunction "IO_L8P_T1_AD10P_15_L17") (pintype "bidirectional"))
    )
    (net (code "135") (name "unconnected-(FPGA1E-IO_L10N_T1_AD15N_35-PadK6)") (class "Default")
      (node (ref "FPGA1") (pin "K6") (pinfunction "IO_L10N_T1_AD15N_35_K6") (pintype "bidirectional"))
    )
  )
)
